# Bus_Definition_V1_1.net
KiCad netlist of a schematic drawn in EAGLE
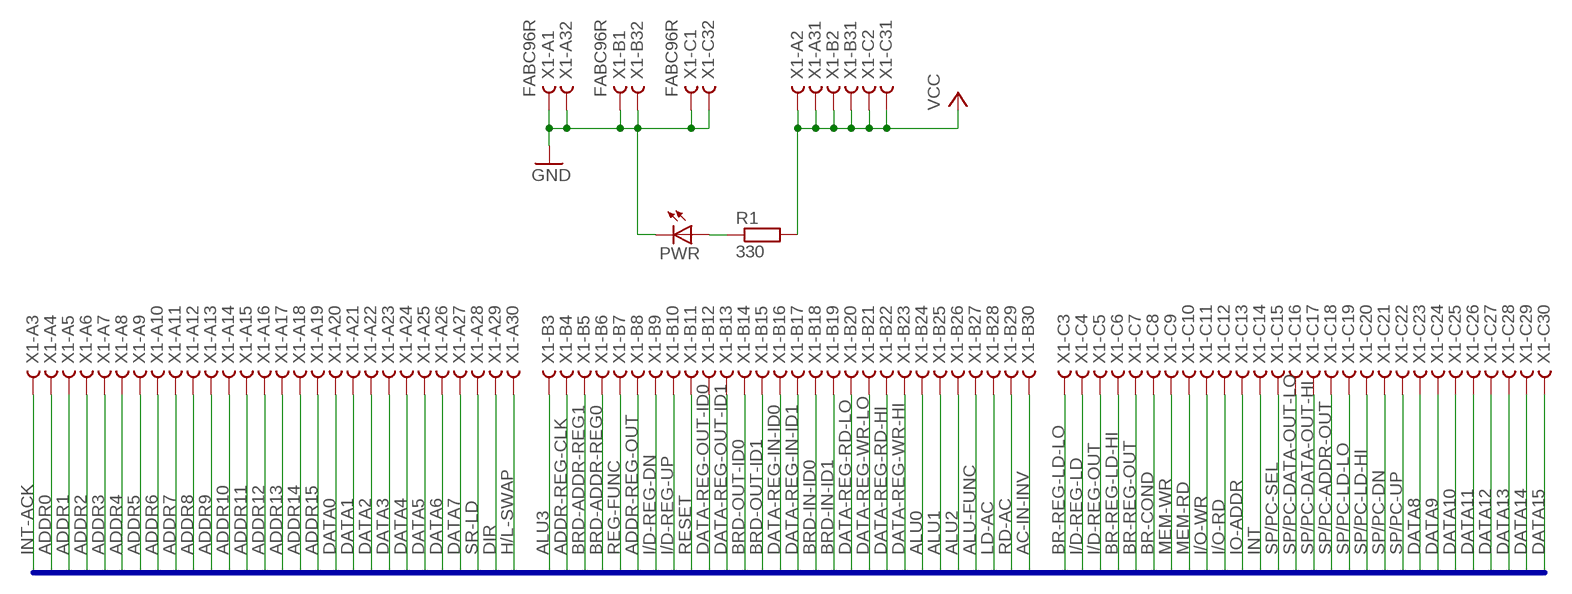
[diagram p0: schematic, sheet 1]

(export (version "E")
  (design (tool "Eeschema 10.0.6"))
  (components
    (comp (ref "PWR")
      (value "LED5MM")
      (footprint "eagle-import:LED5MM")
      (libsource (lib "eagle-import") (part "LED5MM"))
    )
    (comp (ref "R1")
      (value "330")
      (footprint "eagle-import:0207_10")
      (libsource (lib "eagle-import") (part "R0207/10"))
    )
    (comp (ref "X1")
      (value "FABC96R")
      (footprint "eagle-import:FABC96R")
      (libsource (lib "eagle-import") (part "FABC96R"))
    )
  )
  (nets
    (net (code "1") (name "/AC-IN-INV") (class "Default")
      (node (ref "X1") (pin "B30") (pinfunction "B_B30") (pintype "passive"))
    )
    (net (code "2") (name "/ADDR-REG-CLK") (class "Default")
      (node (ref "X1") (pin "B4") (pinfunction "B_B4") (pintype "passive"))
    )
    (net (code "3") (name "/ADDR-REG-OUT") (class "Default")
      (node (ref "X1") (pin "B8") (pinfunction "B_B8") (pintype "passive"))
    )
    (net (code "4") (name "/ADDR0") (class "Default")
      (node (ref "X1") (pin "A4") (pinfunction "B_A4") (pintype "passive"))
    )
    (net (code "5") (name "/ADDR1") (class "Default")
      (node (ref "X1") (pin "A5") (pinfunction "B_A5") (pintype "passive"))
    )
    (net (code "6") (name "/ADDR2") (class "Default")
      (node (ref "X1") (pin "A6") (pinfunction "B_A6") (pintype "passive"))
    )
    (net (code "7") (name "/ADDR3") (class "Default")
      (node (ref "X1") (pin "A7") (pinfunction "B_A7") (pintype "passive"))
    )
    (net (code "8") (name "/ADDR4") (class "Default")
      (node (ref "X1") (pin "A8") (pinfunction "B_A8") (pintype "passive"))
    )
    (net (code "9") (name "/ADDR5") (class "Default")
      (node (ref "X1") (pin "A9") (pinfunction "B_A9") (pintype "passive"))
    )
    (net (code "10") (name "/ADDR6") (class "Default")
      (node (ref "X1") (pin "A10") (pinfunction "B_A10") (pintype "passive"))
    )
    (net (code "11") (name "/ADDR7") (class "Default")
      (node (ref "X1") (pin "A11") (pinfunction "B_A11") (pintype "passive"))
    )
    (net (code "12") (name "/ADDR8") (class "Default")
      (node (ref "X1") (pin "A12") (pinfunction "B_A12") (pintype "passive"))
    )
    (net (code "13") (name "/ADDR9") (class "Default")
      (node (ref "X1") (pin "A13") (pinfunction "B_A13") (pintype "passive"))
    )
    (net (code "14") (name "/ADDR10") (class "Default")
      (node (ref "X1") (pin "A14") (pinfunction "B_A14") (pintype "passive"))
    )
    (net (code "15") (name "/ADDR11") (class "Default")
      (node (ref "X1") (pin "A15") (pinfunction "B_A15") (pintype "passive"))
    )
    (net (code "16") (name "/ADDR12") (class "Default")
      (node (ref "X1") (pin "A16") (pinfunction "B_A16") (pintype "passive"))
    )
    (net (code "17") (name "/ADDR13") (class "Default")
      (node (ref "X1") (pin "A17") (pinfunction "B_A17") (pintype "passive"))
    )
    (net (code "18") (name "/ADDR14") (class "Default")
      (node (ref "X1") (pin "A18") (pinfunction "B_A18") (pintype "passive"))
    )
    (net (code "19") (name "/ADDR15") (class "Default")
      (node (ref "X1") (pin "A19") (pinfunction "B_A19") (pintype "passive"))
    )
    (net (code "20") (name "/ALU-FUNC") (class "Default")
      (node (ref "X1") (pin "B27") (pinfunction "B_B27") (pintype "passive"))
    )
    (net (code "21") (name "/ALU0") (class "Default")
      (node (ref "X1") (pin "B24") (pinfunction "B_B24") (pintype "passive"))
    )
    (net (code "22") (name "/ALU1") (class "Default")
      (node (ref "X1") (pin "B25") (pinfunction "B_B25") (pintype "passive"))
    )
    (net (code "23") (name "/ALU2") (class "Default")
      (node (ref "X1") (pin "B26") (pinfunction "B_B26") (pintype "passive"))
    )
    (net (code "24") (name "/ALU3") (class "Default")
      (node (ref "X1") (pin "B3") (pinfunction "B_B3") (pintype "passive"))
    )
    (net (code "25") (name "/BR-COND") (class "Default")
      (node (ref "X1") (pin "C8") (pinfunction "B_C8") (pintype "passive"))
    )
    (net (code "26") (name "/BR-REG-LD-HI") (class "Default")
      (node (ref "X1") (pin "C6") (pinfunction "B_C6") (pintype "passive"))
    )
    (net (code "27") (name "/BR-REG-LD-LO") (class "Default")
      (node (ref "X1") (pin "C3") (pinfunction "B_C3") (pintype "passive"))
    )
    (net (code "28") (name "/BR-REG-OUT") (class "Default")
      (node (ref "X1") (pin "C7") (pinfunction "B_C7") (pintype "passive"))
    )
    (net (code "29") (name "/BRD-ADDR-REG0") (class "Default")
      (node (ref "X1") (pin "B6") (pinfunction "B_B6") (pintype "passive"))
    )
    (net (code "30") (name "/BRD-ADDR-REG1") (class "Default")
      (node (ref "X1") (pin "B5") (pinfunction "B_B5") (pintype "passive"))
    )
    (net (code "31") (name "/BRD-IN-ID0") (class "Default")
      (node (ref "X1") (pin "B18") (pinfunction "B_B18") (pintype "passive"))
    )
    (net (code "32") (name "/BRD-IN-ID1") (class "Default")
      (node (ref "X1") (pin "B19") (pinfunction "B_B19") (pintype "passive"))
    )
    (net (code "33") (name "/BRD-OUT-ID0") (class "Default")
      (node (ref "X1") (pin "B14") (pinfunction "B_B14") (pintype "passive"))
    )
    (net (code "34") (name "/BRD-OUT-ID1") (class "Default")
      (node (ref "X1") (pin "B15") (pinfunction "B_B15") (pintype "passive"))
    )
    (net (code "35") (name "/DATA-REG-IN-ID0") (class "Default")
      (node (ref "X1") (pin "B16") (pinfunction "B_B16") (pintype "passive"))
    )
    (net (code "36") (name "/DATA-REG-IN-ID1") (class "Default")
      (node (ref "X1") (pin "B17") (pinfunction "B_B17") (pintype "passive"))
    )
    (net (code "37") (name "/DATA-REG-OUT-ID0") (class "Default")
      (node (ref "X1") (pin "B12") (pinfunction "B_B12") (pintype "passive"))
    )
    (net (code "38") (name "/DATA-REG-OUT-ID1") (class "Default")
      (node (ref "X1") (pin "B13") (pinfunction "B_B13") (pintype "passive"))
    )
    (net (code "39") (name "/DATA-REG-RD-HI") (class "Default")
      (node (ref "X1") (pin "B22") (pinfunction "B_B22") (pintype "passive"))
    )
    (net (code "40") (name "/DATA-REG-RD-LO") (class "Default")
      (node (ref "X1") (pin "B20") (pinfunction "B_B20") (pintype "passive"))
    )
    (net (code "41") (name "/DATA-REG-WR-HI") (class "Default")
      (node (ref "X1") (pin "B23") (pinfunction "B_B23") (pintype "passive"))
    )
    (net (code "42") (name "/DATA-REG-WR-LO") (class "Default")
      (node (ref "X1") (pin "B21") (pinfunction "B_B21") (pintype "passive"))
    )
    (net (code "43") (name "/DATA0") (class "Default")
      (node (ref "X1") (pin "A20") (pinfunction "B_A20") (pintype "passive"))
    )
    (net (code "44") (name "/DATA1") (class "Default")
      (node (ref "X1") (pin "A21") (pinfunction "B_A21") (pintype "passive"))
    )
    (net (code "45") (name "/DATA2") (class "Default")
      (node (ref "X1") (pin "A22") (pinfunction "B_A22") (pintype "passive"))
    )
    (net (code "46") (name "/DATA3") (class "Default")
      (node (ref "X1") (pin "A23") (pinfunction "B_A23") (pintype "passive"))
    )
    (net (code "47") (name "/DATA4") (class "Default")
      (node (ref "X1") (pin "A24") (pinfunction "B_A24") (pintype "passive"))
    )
    (net (code "48") (name "/DATA5") (class "Default")
      (node (ref "X1") (pin "A25") (pinfunction "B_A25") (pintype "passive"))
    )
    (net (code "49") (name "/DATA6") (class "Default")
      (node (ref "X1") (pin "A26") (pinfunction "B_A26") (pintype "passive"))
    )
    (net (code "50") (name "/DATA7") (class "Default")
      (node (ref "X1") (pin "A27") (pinfunction "B_A27") (pintype "passive"))
    )
    (net (code "51") (name "/DATA8") (class "Default")
      (node (ref "X1") (pin "C23") (pinfunction "B_C23") (pintype "passive"))
    )
    (net (code "52") (name "/DATA9") (class "Default")
      (node (ref "X1") (pin "C24") (pinfunction "B_C24") (pintype "passive"))
    )
    (net (code "53") (name "/DATA10") (class "Default")
      (node (ref "X1") (pin "C25") (pinfunction "B_C25") (pintype "passive"))
    )
    (net (code "54") (name "/DATA11") (class "Default")
      (node (ref "X1") (pin "C26") (pinfunction "B_C26") (pintype "passive"))
    )
    (net (code "55") (name "/DATA12") (class "Default")
      (node (ref "X1") (pin "C27") (pinfunction "B_C27") (pintype "passive"))
    )
    (net (code "56") (name "/DATA13") (class "Default")
      (node (ref "X1") (pin "C28") (pinfunction "B_C28") (pintype "passive"))
    )
    (net (code "57") (name "/DATA14") (class "Default")
      (node (ref "X1") (pin "C29") (pinfunction "B_C29") (pintype "passive"))
    )
    (net (code "58") (name "/DATA15") (class "Default")
      (node (ref "X1") (pin "C30") (pinfunction "B_C30") (pintype "passive"))
    )
    (net (code "59") (name "/DIR") (class "Default")
      (node (ref "X1") (pin "A29") (pinfunction "B_A29") (pintype "passive"))
    )
    (net (code "60") (name "/H{slash}L-SWAP") (class "Default")
      (node (ref "X1") (pin "A30") (pinfunction "B_A30") (pintype "passive"))
    )
    (net (code "61") (name "/INT") (class "Default")
      (node (ref "X1") (pin "C14") (pinfunction "B_C14") (pintype "passive"))
    )
    (net (code "62") (name "/INT-ACK") (class "Default")
      (node (ref "X1") (pin "A3") (pinfunction "B_A3") (pintype "passive"))
    )
    (net (code "63") (name "/IO-ADDR") (class "Default")
      (node (ref "X1") (pin "C13") (pinfunction "B_C13") (pintype "passive"))
    )
    (net (code "64") (name "/I{slash}D-REG-DN") (class "Default")
      (node (ref "X1") (pin "B9") (pinfunction "B_B9") (pintype "passive"))
    )
    (net (code "65") (name "/I{slash}D-REG-LD") (class "Default")
      (node (ref "X1") (pin "C4") (pinfunction "B_C4") (pintype "passive"))
    )
    (net (code "66") (name "/I{slash}D-REG-OUT") (class "Default")
      (node (ref "X1") (pin "C5") (pinfunction "B_C5") (pintype "passive"))
    )
    (net (code "67") (name "/I{slash}D-REG-UP") (class "Default")
      (node (ref "X1") (pin "B10") (pinfunction "B_B10") (pintype "passive"))
    )
    (net (code "68") (name "/I{slash}O-RD") (class "Default")
      (node (ref "X1") (pin "C12") (pinfunction "B_C12") (pintype "passive"))
    )
    (net (code "69") (name "/I{slash}O-WR") (class "Default")
      (node (ref "X1") (pin "C11") (pinfunction "B_C11") (pintype "passive"))
    )
    (net (code "70") (name "/LD-AC") (class "Default")
      (node (ref "X1") (pin "B28") (pinfunction "B_B28") (pintype "passive"))
    )
    (net (code "71") (name "/MEM-RD") (class "Default")
      (node (ref "X1") (pin "C10") (pinfunction "B_C10") (pintype "passive"))
    )
    (net (code "72") (name "/MEM-WR") (class "Default")
      (node (ref "X1") (pin "C9") (pinfunction "B_C9") (pintype "passive"))
    )
    (net (code "73") (name "/RD-AC") (class "Default")
      (node (ref "X1") (pin "B29") (pinfunction "B_B29") (pintype "passive"))
    )
    (net (code "74") (name "/REG-FUNC") (class "Default")
      (node (ref "X1") (pin "B7") (pinfunction "B_B7") (pintype "passive"))
    )
    (net (code "75") (name "/RESET") (class "Default")
      (node (ref "X1") (pin "B11") (pinfunction "B_B11") (pintype "passive"))
    )
    (net (code "76") (name "/SP{slash}PC-ADDR-OUT") (class "Default")
      (node (ref "X1") (pin "C18") (pinfunction "B_C18") (pintype "passive"))
    )
    (net (code "77") (name "/SP{slash}PC-DATA-OUT-HI") (class "Default")
      (node (ref "X1") (pin "C17") (pinfunction "B_C17") (pintype "passive"))
    )
    (net (code "78") (name "/SP{slash}PC-DATA-OUT-LO") (class "Default")
      (node (ref "X1") (pin "C16") (pinfunction "B_C16") (pintype "passive"))
    )
    (net (code "79") (name "/SP{slash}PC-DN") (class "Default")
      (node (ref "X1") (pin "C21") (pinfunction "B_C21") (pintype "passive"))
    )
    (net (code "80") (name "/SP{slash}PC-LD-HI") (class "Default")
      (node (ref "X1") (pin "C20") (pinfunction "B_C20") (pintype "passive"))
    )
    (net (code "81") (name "/SP{slash}PC-LD-LO") (class "Default")
      (node (ref "X1") (pin "C19") (pinfunction "B_C19") (pintype "passive"))
    )
    (net (code "82") (name "/SP{slash}PC-SEL") (class "Default")
      (node (ref "X1") (pin "C15") (pinfunction "B_C15") (pintype "passive"))
    )
    (net (code "83") (name "/SP{slash}PC-UP") (class "Default")
      (node (ref "X1") (pin "C22") (pinfunction "B_C22") (pintype "passive"))
    )
    (net (code "84") (name "/SR-LD") (class "Default")
      (node (ref "X1") (pin "A28") (pinfunction "B_A28") (pintype "passive"))
    )
    (net (code "85") (name "GND") (class "Default")
      (node (ref "PWR") (pin "K") (pinfunction "C_K") (pintype "passive"))
      (node (ref "X1") (pin "A1") (pinfunction "B_A1") (pintype "passive"))
      (node (ref "X1") (pin "A32") (pinfunction "B_A32") (pintype "passive"))
      (node (ref "X1") (pin "B1") (pinfunction "B_B1") (pintype "passive"))
      (node (ref "X1") (pin "B32") (pinfunction "B_B32") (pintype "passive"))
      (node (ref "X1") (pin "C1") (pinfunction "B_C1") (pintype "passive"))
      (node (ref "X1") (pin "C32") (pinfunction "B_C32") (pintype "passive"))
    )
    (net (code "86") (name "Net-(PWR-PadA)") (class "Default")
      (node (ref "PWR") (pin "A") (pinfunction "A_A") (pintype "passive"))
      (node (ref "R1") (pin "1") (pinfunction "1_1") (pintype "passive"))
    )
    (net (code "87") (name "VCC") (class "Default")
      (node (ref "R1") (pin "2") (pinfunction "2_2") (pintype "passive"))
      (node (ref "X1") (pin "A2") (pinfunction "B_A2") (pintype "passive"))
      (node (ref "X1") (pin "A31") (pinfunction "B_A31") (pintype "passive"))
      (node (ref "X1") (pin "B2") (pinfunction "B_B2") (pintype "passive"))
      (node (ref "X1") (pin "B31") (pinfunction "B_B31") (pintype "passive"))
      (node (ref "X1") (pin "C2") (pinfunction "B_C2") (pintype "passive"))
      (node (ref "X1") (pin "C31") (pinfunction "B_C31") (pintype "passive"))
    )
  )
)
